# LNA.net
KiCad netlist of a schematic drawn in Altium Designer
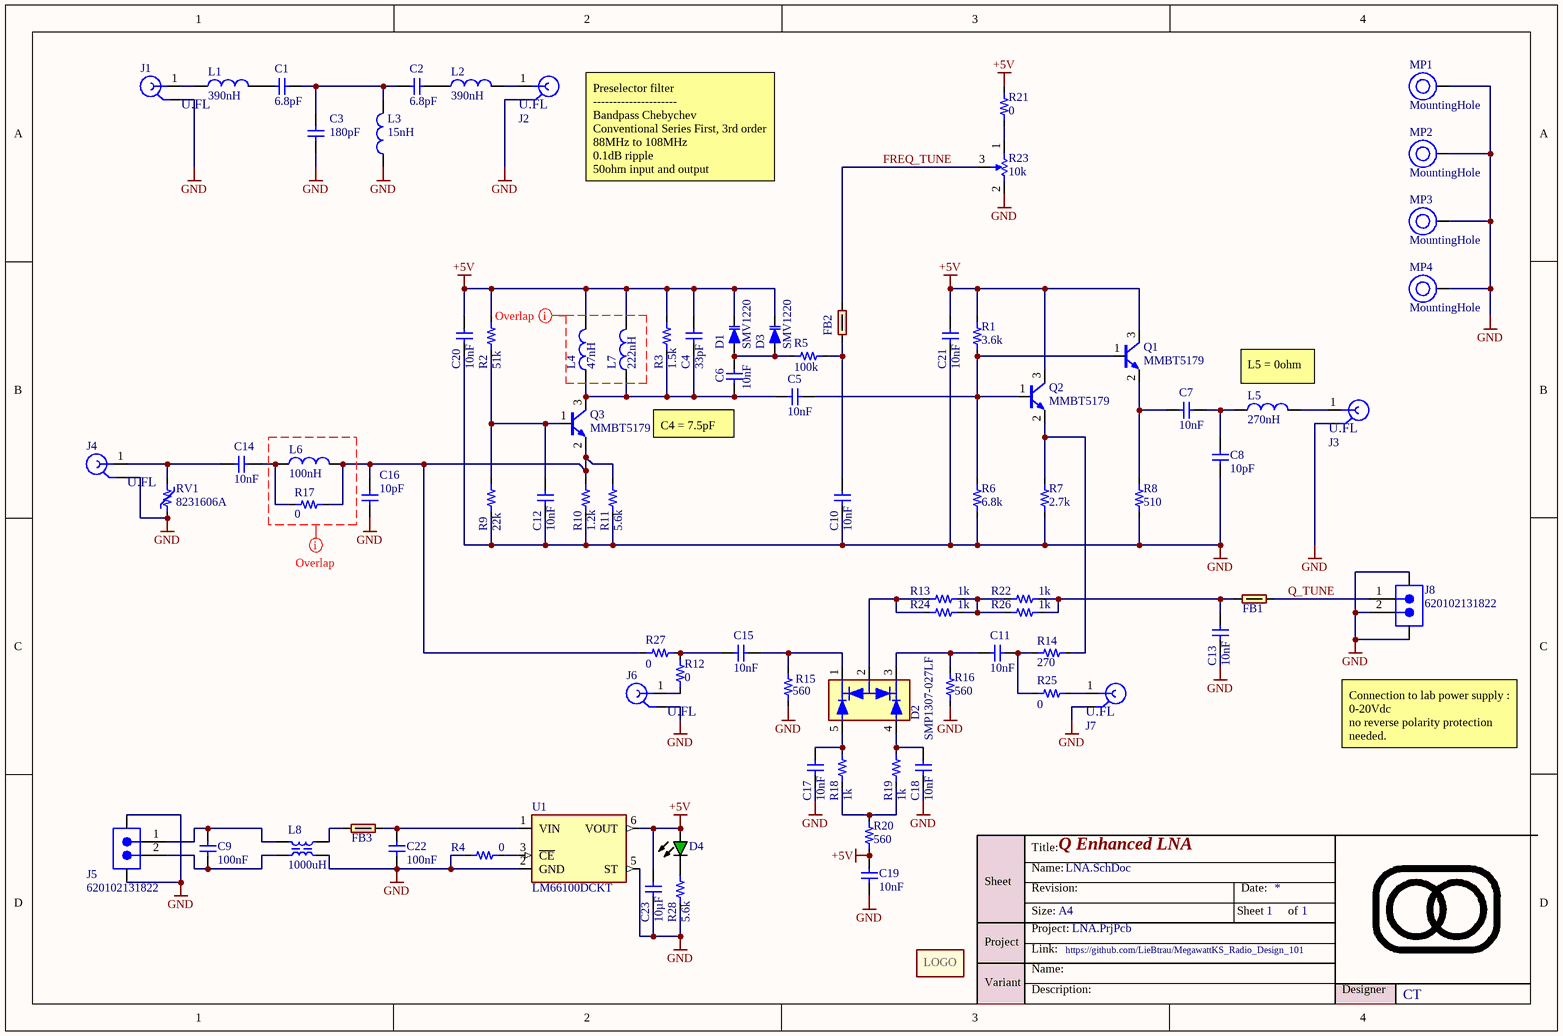
[diagram p0: LNA.SchDoc]

(export (version "E")
  (design (tool "Eeschema 10.0.6"))
  (components
    (comp (ref "C1")
      (value "6.8pF")
      (footprint "0603-C-N")
      (description "WCAP-CSGP Multilayer Ceramic Chip Capacitor, General Purpose, size 0603, NP0, 6.8pF, 50VDC")
      (fields
        (field (name "TOLERANCE") "0.5pF")
        (field (name "Comment") "Capacitor 6.8pF +/-0.5pF 50V NP0 0603")
      )
      (libsource (lib "7c7 Engineering") (part "CAP-NP-2"))
    )
    (comp (ref "C2")
      (value "6.8pF")
      (footprint "0603-C-N")
      (description "WCAP-CSGP Multilayer Ceramic Chip Capacitor, General Purpose, size 0603, NP0, 6.8pF, 50VDC")
      (fields
        (field (name "TOLERANCE") "0.5pF")
        (field (name "Comment") "Capacitor 6.8pF +/-0.5pF 50V NP0 0603")
      )
      (libsource (lib "7c7 Engineering") (part "CAP-NP-2"))
    )
    (comp (ref "C3")
      (value "180pF")
      (footprint "0603-C-N")
      (description "Cap Ceramic 180pF 100V C0G 5% SMD 0603 125°C Paper T/R")
      (fields (field (name "TOLERANCE") "5%") (field (name "JLCPCB PART #") "C107041"))
      (libsource (lib "7c7 Engineering") (part "CAP-NP-2"))
    )
    (comp (ref "C4")
      (value "33pF")
      (footprint "0603-C-N")
      (description "WCAP-CSGP Multilayer Ceramic Chip Capacitor, General Purpose, size 0603, NP0, 33pF, 50VDC")
      (fields (field (name "TOLERANCE") "5%") (field (name "Comment") "Capacitor 33pF +/-5% 50V NP0 0603"))
      (libsource (lib "7c7 Engineering") (part "CAP-NP-2"))
    )
    (comp (ref "C5")
      (value "10nF")
      (footprint "0603-C-N")
      (description "Multilayer Ceramic Capacitor, Grm Series, 0.01 F, 5%, C0g / Np0, 50 V, 0603 [1608 Metric]")
      (fields (field (name "VOLTAGE") "50V") (field (name "TOLERANCE") "5%"))
      (libsource (lib "7c7 Engineering") (part "CAP-NP-2"))
    )
    (comp (ref "C6")
      (value "10nF")
      (footprint "0603-C-N")
      (description "Multilayer Ceramic Capacitor, Grm Series, 0.01 F, 5%, C0g / Np0, 50 V, 0603 [1608 Metric]")
      (fields (field (name "VOLTAGE") "50V") (field (name "TOLERANCE") "5%"))
      (libsource (lib "7c7 Engineering") (part "CAP-NP-2"))
    )
    (comp (ref "C7")
      (value "10nF")
      (footprint "0603-C-N")
      (description "Multilayer Ceramic Capacitor, Grm Series, 0.01 F, 5%, C0g / Np0, 50 V, 0603 [1608 Metric]")
      (fields (field (name "VOLTAGE") "50V") (field (name "TOLERANCE") "5%"))
      (libsource (lib "7c7 Engineering") (part "CAP-NP-2"))
    )
    (comp (ref "C8")
      (value "10pF")
      (footprint "0603-C-N")
      (description "WCAP-CSGP Multilayer Ceramic Chip Capacitor, General Purpose, size 0603, NP0, 10pF, 50VDC")
      (fields (field (name "JLCPCB PART #") "C106245") (field (name "TOLERANCE") "5%"))
      (libsource (lib "7c7 Engineering") (part "CAP-NP-2"))
    )
    (comp (ref "C9")
      (value "100nF")
      (footprint "0603-C-N")
      (description "WCAP-CSGP Multilayer Ceramic Chip Capacitor, General Purpose, size 0603, X7R, 100nF, 50VDC")
      (fields (field (name "TOLERANCE") "10%") (field (name "JLCPCB PART #") "C14663"))
      (libsource (lib "7c7 Engineering") (part "CAP-NP-2"))
    )
    (comp (ref "C10")
      (value "10nF")
      (footprint "0603-C-N")
      (description "Multilayer Ceramic Capacitor, Grm Series, 0.01 F, 5%, C0g / Np0, 50 V, 0603 [1608 Metric]")
      (fields (field (name "VOLTAGE") "50V") (field (name "TOLERANCE") "5%"))
      (libsource (lib "7c7 Engineering") (part "CAP-NP-2"))
    )
    (comp (ref "C11")
      (value "10nF")
      (footprint "0603-C-N")
      (description "Multilayer Ceramic Capacitor, Grm Series, 0.01 F, 5%, C0g / Np0, 50 V, 0603 [1608 Metric]")
      (fields (field (name "VOLTAGE") "50V") (field (name "TOLERANCE") "5%"))
      (libsource (lib "7c7 Engineering") (part "CAP-NP-2"))
    )
    (comp (ref "C12")
      (value "10nF")
      (footprint "0603-C-N")
      (description "Multilayer Ceramic Capacitor, Grm Series, 0.01 F, 5%, C0g / Np0, 50 V, 0603 [1608 Metric]")
      (fields (field (name "VOLTAGE") "50V") (field (name "TOLERANCE") "5%"))
      (libsource (lib "7c7 Engineering") (part "CAP-NP-2"))
    )
    (comp (ref "C13")
      (value "10nF")
      (footprint "0603-C-N")
      (description "Multilayer Ceramic Capacitor, Grm Series, 0.01 F, 5%, C0g / Np0, 50 V, 0603 [1608 Metric]")
      (fields (field (name "VOLTAGE") "50V") (field (name "TOLERANCE") "5%"))
      (libsource (lib "7c7 Engineering") (part "CAP-NP-2"))
    )
    (comp (ref "C14")
      (value "10nF")
      (footprint "0603-C-N")
      (description "Multilayer Ceramic Capacitor, Grm Series, 0.01 F, 5%, C0g / Np0, 50 V, 0603 [1608 Metric]")
      (fields (field (name "VOLTAGE") "50V") (field (name "TOLERANCE") "5%"))
      (libsource (lib "7c7 Engineering") (part "CAP-NP-2"))
    )
    (comp (ref "C15")
      (value "10nF")
      (footprint "0603-C-N")
      (description "Multilayer Ceramic Capacitor, Grm Series, 0.01 F, 5%, C0g / Np0, 50 V, 0603 [1608 Metric]")
      (fields (field (name "VOLTAGE") "50V") (field (name "TOLERANCE") "5%"))
      (libsource (lib "7c7 Engineering") (part "CAP-NP-2"))
    )
    (comp (ref "C16")
      (value "10pF")
      (footprint "0603-C-N")
      (description "WCAP-CSGP Multilayer Ceramic Chip Capacitor, General Purpose, size 0603, NP0, 10pF, 50VDC")
      (fields (field (name "TOLERANCE") "5%") (field (name "JLCPCB PART #") "C106245"))
      (libsource (lib "7c7 Engineering") (part "CAP-NP-2"))
    )
    (comp (ref "C17")
      (value "10nF")
      (footprint "0603-C-N")
      (description "Multilayer Ceramic Capacitor, Grm Series, 0.01 F, 5%, C0g / Np0, 50 V, 0603 [1608 Metric]")
      (fields (field (name "VOLTAGE") "50V") (field (name "TOLERANCE") "5%"))
      (libsource (lib "7c7 Engineering") (part "CAP-NP-2"))
    )
    (comp (ref "C18")
      (value "10nF")
      (footprint "0603-C-N")
      (description "Multilayer Ceramic Capacitor, Grm Series, 0.01 F, 5%, C0g / Np0, 50 V, 0603 [1608 Metric]")
      (fields (field (name "VOLTAGE") "50V") (field (name "TOLERANCE") "5%"))
      (libsource (lib "7c7 Engineering") (part "CAP-NP-2"))
    )
    (comp (ref "C19")
      (value "10nF")
      (footprint "0603-C-N")
      (description "Multilayer Ceramic Capacitor, Grm Series, 0.01 F, 5%, C0g / Np0, 50 V, 0603 [1608 Metric]")
      (fields (field (name "VOLTAGE") "50V") (field (name "TOLERANCE") "5%"))
      (libsource (lib "7c7 Engineering") (part "CAP-NP-2"))
    )
    (comp (ref "C20")
      (value "10nF")
      (footprint "0603-C-N")
      (description "Multilayer Ceramic Capacitor, Grm Series, 0.01 F, 5%, C0g / Np0, 50 V, 0603 [1608 Metric]")
      (fields (field (name "VOLTAGE") "50V") (field (name "TOLERANCE") "5%"))
      (libsource (lib "7c7 Engineering") (part "CAP-NP-2"))
    )
    (comp (ref "C21")
      (value "10nF")
      (footprint "0603-C-N")
      (description "Multilayer Ceramic Capacitor, Grm Series, 0.01 F, 5%, C0g / Np0, 50 V, 0603 [1608 Metric]")
      (fields (field (name "VOLTAGE") "50V") (field (name "TOLERANCE") "5%"))
      (libsource (lib "7c7 Engineering") (part "CAP-NP-2"))
    )
    (comp (ref "C22")
      (value "100nF")
      (footprint "0603-C-N")
      (description "WCAP-CSGP Multilayer Ceramic Chip Capacitor, General Purpose, size 0603, X7R, 100nF, 50VDC")
      (fields (field (name "TOLERANCE") "10%") (field (name "JLCPCB PART #") "C14663"))
      (libsource (lib "7c7 Engineering") (part "CAP-NP-2"))
    )
    (comp (ref "C23")
      (value "10µF")
      (footprint "WCAP-CSGP_1210_L3.2W2.5H2.5")
      (description "WCAP-CSGP Multilayer Ceramic Chip Capacitor, General Purpose, size 1210, X7R, 10µF, 50VDC")
      (fields (field (name "JLCPCB PART #") "C77102") (field (name "TOLERANCE") "10%"))
      (libsource (lib "7c7 Engineering") (part "CAP-NP-2"))
    )
    (comp (ref "D1")
      (value "SMV1220")
      (footprint "FP-SOD523-MFG")
      (description "Diode, Varactor, SC79 N-Type")
      (fields (field (name "Comment") "SMV1220-079LF"))
      (libsource (lib "7c7 Engineering") (part "DIODE-VARACTOR"))
    )
    (comp (ref "D2")
      (value "SMP1307-027LF")
      (footprint "SOT25-N")
      (description "Dio Sw 0.85V 200V 10MA SOT5")
      (libsource (lib "7c7 Engineering") (part "SMP1307-027LF-Symbol-1"))
    )
    (comp (ref "D3")
      (value "SMV1220")
      (footprint "FP-SOD523-MFG")
      (description "Diode, Varactor, SC79 N-Type")
      (fields (field (name "Comment") "SMV1220-079LF"))
      (libsource (lib "7c7 Engineering") (part "DIODE-VARACTOR"))
    )
    (comp (ref "D4")
      (value "150060GS84000")
      (footprint "WL-SMCW_0603_150060xx8x000")
      (description "WL-SMCW Mono-color Chip LED Waterclear, size 0603, Green, 3.3V, 40°")
      (fields (field (name "JLCPCB PART #") "C7429914") (field (name "MANUFACTURER") "Wurth Elektronik"))
      (libsource (lib "7c7 Engineering") (part "LED-GREEN-2"))
    )
    (comp (ref "FB1")
      (value "742792662")
      (footprint "0603-FB-N")
      (description "WE-CBF SMT EMI Suppression Ferrite Bead, size 0603, 1000O, 0.83A")
      (fields (field (name "JLCPCB PART #") "C180490") (field (name "MANUFACTURER") "Wurth Elektronik"))
      (libsource (lib "") (part "IND_BEAD_1"))
    )
    (comp (ref "FB2")
      (value "742792662")
      (footprint "0603-FB-N")
      (description "WE-CBF SMT EMI Suppression Ferrite Bead, size 0603, 1000O, 0.83A")
      (fields (field (name "JLCPCB PART #") "C180490") (field (name "MANUFACTURER") "Wurth Elektronik"))
      (libsource (lib "7c7 Engineering") (part "IND_BEAD"))
    )
    (comp (ref "FB3")
      (value "742792662")
      (footprint "0603-FB-N")
      (description "WE-CBF SMT EMI Suppression Ferrite Bead, size 0603, 1000O, 0.83A")
      (fields (field (name "JLCPCB PART #") "C180490") (field (name "MANUFACTURER") "Wurth Elektronik"))
      (libsource (lib "") (part "IND_BEAD_1"))
    )
    (comp (ref "J1")
      (value "U.FL-R-SMT(10)")
      (footprint "HRS-U.FL-R-SMT_V")
      (fields (field (name "JLCPCB PART #") "C88373") (field (name "MANUFACTURER") "Hirose Electric"))
      (libsource (lib "") (part "CN_COAX_1"))
    )
    (comp (ref "J2")
      (value "U.FL-R-SMT(10)")
      (footprint "HRS-U.FL-R-SMT_V")
      (fields (field (name "JLCPCB PART #") "C88373") (field (name "MANUFACTURER") "Hirose Electric"))
      (libsource (lib "7c7 Engineering") (part "CN_COAX"))
    )
    (comp (ref "J3")
      (value "U.FL-R-SMT(10)")
      (footprint "HRS-U.FL-R-SMT_V")
      (fields (field (name "JLCPCB PART #") "C88373") (field (name "MANUFACTURER") "Hirose Electric"))
      (libsource (lib "7c7 Engineering") (part "CN_COAX"))
    )
    (comp (ref "J4")
      (value "U.FL-R-SMT(10)")
      (footprint "HRS-U.FL-R-SMT_V")
      (fields (field (name "JLCPCB PART #") "C88373") (field (name "MANUFACTURER") "Hirose Electric"))
      (libsource (lib "") (part "CN_COAX_1"))
    )
    (comp (ref "J5")
      (value "620102131822")
      (footprint "620102131822")
      (description "WR-WTB SMT Male Horizontal Shrouded Header, pitch 2mm, 2p")
      (fields
        (field (name "JLCPCB PART #") "C295747")
        (field (name "PAGE PART #") "K620102131822")
        (field (name "PUBLISHER") "Wurth Elektronik")
      )
      (libsource (lib "7c7 Engineering") (part "HDR_2P_2MP"))
    )
    (comp (ref "J6")
      (value "U.FL-R-SMT(10)")
      (footprint "HRS-U.FL-R-SMT_V")
      (fields (field (name "JLCPCB PART #") "C88373") (field (name "MANUFACTURER") "Hirose Electric"))
      (libsource (lib "") (part "CN_COAX_1"))
    )
    (comp (ref "J7")
      (value "U.FL-R-SMT(10)")
      (footprint "HRS-U.FL-R-SMT_V")
      (fields (field (name "JLCPCB PART #") "C88373") (field (name "MANUFACTURER") "Hirose Electric"))
      (libsource (lib "7c7 Engineering") (part "CN_COAX"))
    )
    (comp (ref "J8")
      (value "620102131822")
      (footprint "620102131822")
      (description "WR-WTB SMT Male Horizontal Shrouded Header, pitch 2mm, 2p")
      (fields
        (field (name "JLCPCB PART #") "C295747")
        (field (name "PAGE PART #") "K620102131822")
        (field (name "PUBLISHER") "Wurth Elektronik")
      )
      (libsource (lib "7c7 Engineering") (part "HDR_2P_2MP"))
    )
    (comp (ref "L1")
      (value "744762239GA")
      (footprint "WE-KI_1008")
      (description "WE-KI SMT Wire Wound Ceramic Inductor, size 1008, 390nH, 0.47A")
      (fields (field (name "INDUCTANCE") "390nH") (field (name "MANUFACTURER") "Wurth Elektronik"))
      (libsource (lib "7c7 Engineering") (part "IND"))
    )
    (comp (ref "L2")
      (value "744762239GA")
      (footprint "WE-KI_1008")
      (description "WE-KI SMT Wire Wound Ceramic Inductor, size 1008, 390nH, 0.47A")
      (fields (field (name "INDUCTANCE") "390nH") (field (name "MANUFACTURER") "Wurth Elektronik"))
      (libsource (lib "7c7 Engineering") (part "IND"))
    )
    (comp (ref "L3")
      (value "744762115GA")
      (footprint "WE-KI_1008")
      (description "WE-KI SMT Wire Wound Ceramic Inductor, size 1008, 15nH, 1A")
      (fields (field (name "INDUCTANCE") "15nH") (field (name "MANUFACTURER") "Wurth Elektronik"))
      (libsource (lib "7c7 Engineering") (part "IND"))
    )
    (comp (ref "L4")
      (value "744912147")
      (footprint "WE-CAIR_4248")
      (description "WE-CAIR SMT Air Coil, size 4248, 47nH, 3A, 5.6mO")
      (fields (field (name "MANUFACTURER") "Wurth Elektronik") (field (name "INDUCTANCE") "47nH"))
      (libsource (lib "7c7 Engineering") (part "IND"))
    )
    (comp (ref "L5")
      (value "744762227GA")
      (footprint "WE-KI_1008")
      (description "WE-KI SMT Wire Wound Ceramic Inductor, size 1008, 270nH, 0.6A")
      (fields (field (name "MANUFACTURER") "Wurth Elektronik") (field (name "INDUCTANCE") "270nH"))
      (libsource (lib "7c7 Engineering") (part "IND"))
    )
    (comp (ref "L6")
      (value "744762210GA")
      (footprint "WE-KI_1008")
      (description "WE-KI SMT Wire Wound Ceramic Inductor, size 1008, 100nH, 1A")
      (fields (field (name "MANUFACTURER") "Wurth Elektronik") (field (name "INDUCTANCE") "100nH"))
      (libsource (lib "7c7 Engineering") (part "IND"))
    )
    (comp (ref "L7")
      (value "744918222")
      (footprint "WE-CAIR_5910")
      (description "WE-CAIR SMT Air Coil, size 5910, 222nH, 3A, 35mO")
      (fields (field (name "INDUCTANCE") "222nH") (field (name "MANUFACTURER") "Wurth Elektronik"))
      (libsource (lib "7c7 Engineering") (part "IND"))
    )
    (comp (ref "L8")
      (value "744222")
      (footprint "WE-SL2_L9.2W6H5")
      (description "WE-SL2 SMT Common Mode Line Filter, 1000uH, 0.8A, 0.207Ohm")
      (fields
        (field (name "INDUCTANCE") "1000uH")
        (field (name "MANUFACTURER") "Wurth Elektronik")
        (field (name "JLCPCB PART #") "C2829007")
      )
      (libsource (lib "7c7 Engineering") (part "CM-choke"))
    )
    (comp (ref "M1")
      (value "Logo")
      (footprint "LOGO_9x6mm")
      (libsource (lib "Integrated_Library_LieBtrau") (part "Logo"))
    )
    (comp (ref "MP1")
      (value "MountingHole")
      (footprint "PTH-M3D6.5_VIA-RING")
      (libsource (lib "7c7 Engineering") (part "MECH_NO_BOM"))
    )
    (comp (ref "MP2")
      (value "MountingHole")
      (footprint "PTH-M3D6.5_VIA-RING")
      (libsource (lib "7c7 Engineering") (part "MECH_NO_BOM"))
    )
    (comp (ref "MP3")
      (value "MountingHole")
      (footprint "PTH-M3D6.5_VIA-RING")
      (libsource (lib "7c7 Engineering") (part "MECH_NO_BOM"))
    )
    (comp (ref "MP4")
      (value "MountingHole")
      (footprint "PTH-M3D6.5_VIA-RING")
      (libsource (lib "7c7 Engineering") (part "MECH_NO_BOM"))
    )
    (comp (ref "Q1")
      (value "MMBT5179")
      (footprint "SOT-23-3-N")
      (description "MMBT5179 Series 12 V CE Breakdown .05 A NPN RF Transistor - SOT-23")
      (fields (field (name "JLCPCB PART #") "C416012"))
      (libsource (lib "7c7 Engineering") (part "BJT-NPN-BEC"))
    )
    (comp (ref "Q2")
      (value "MMBT5179")
      (footprint "SOT-23-3-N")
      (description "MMBT5179 Series 12 V CE Breakdown .05 A NPN RF Transistor - SOT-23")
      (fields (field (name "JLCPCB PART #") "C416012"))
      (libsource (lib "7c7 Engineering") (part "BJT-NPN-BEC"))
    )
    (comp (ref "Q3")
      (value "MMBT5179")
      (footprint "SOT-23-3-N")
      (description "MMBT5179 Series 12 V CE Breakdown .05 A NPN RF Transistor - SOT-23")
      (fields (field (name "JLCPCB PART #") "C416012"))
      (libsource (lib "7c7 Engineering") (part "BJT-NPN-BEC"))
    )
    (comp (ref "R1")
      (value "3.6k")
      (footprint "0603-R-N")
      (description "Res Thick Film 0603 3.6K Ohm 1% 0.1W(1/10W) ±100ppm/°C Pad SMD T/R")
      (fields
        (field (name "JLCPCB PART #") "C22980")
        (field (name "Comment") "Resistor 3.6k +/-0.1W 1% 0603")
      )
      (libsource (lib "7c7 Engineering") (part "RES"))
    )
    (comp (ref "R2")
      (value "51k")
      (footprint "0603-R-N")
      (description "100Mw Thick Film Resistors 100Ppm/ 1% 51K 0603 Chip Resistor Surface Mount Rohs")
      (fields (field (name "TOLERANCE") "1%") (field (name "JLCPCB PART #") "C23196"))
      (libsource (lib "7c7 Engineering") (part "RES"))
    )
    (comp (ref "R3")
      (value "1.5k")
      (footprint "0603-R-N")
      (description "Chip Resistor, Thick Film, General Purpose, 0603, 100mW, 50V, 1.5 kOhm, +/-1%")
      (fields (field (name "TOLERANCE") "1%") (field (name "JLCPCB PART #") "C22843"))
      (libsource (lib "7c7 Engineering") (part "RES"))
    )
    (comp (ref "R4")
      (value "0")
      (footprint "0603-R-N")
      (description "Chip Jumper, Thick Film, Jumper, 0603, 100mW, 1A, 0 Ohm, <50 mOhm")
      (fields (field (name "FLIR PART #") "YRES0E-1") (field (name "TOLERANCE") "50 mOhm"))
      (libsource (lib "7c7 Engineering") (part "RES"))
    )
    (comp (ref "R5")
      (value "100k")
      (footprint "0603-R-N")
      (description "Chip Resistor, Thick Film, General Purpose, 0603, 100mW, 50V, 100 kOhm, +/-1%")
      (fields (field (name "TOLERANCE") "1%") (field (name "JLCPCB PART #") "C25803"))
      (libsource (lib "7c7 Engineering") (part "RES"))
    )
    (comp (ref "R6")
      (value "6.8k")
      (footprint "0603-R-N")
      (description "Res Thick Film 0603 6.8K Ohm 1% 0.1W(1/10W) ±100ppm/C Pad SMD T/R")
      (fields (field (name "TOLERANCE") "1%") (field (name "JLCPCB PART #") "C23212"))
      (libsource (lib "7c7 Engineering") (part "RES"))
    )
    (comp (ref "R7")
      (value "2.7k")
      (footprint "0603-R-N")
      (description "Res Thick Film 0603 2.7K Ohm 1% 0.1W(1/10W) ±100ppm/C Pad SMD Automotive T/R")
      (fields (field (name "TOLERANCE") "1%") (field (name "JLCPCB PART #") "C13167"))
      (libsource (lib "7c7 Engineering") (part "RES"))
    )
    (comp (ref "R8")
      (value "510")
      (footprint "0603-R-N")
      (description "SMD Chip Resistor, 510 Ohm, ± 1%, 100 mW, 0603 [1608 Metric], Thick Film, General Purpose")
      (fields (field (name "JLCPCB PART #") "C23193") (field (name "TOLERANCE") "1%"))
      (libsource (lib "7c7 Engineering") (part "RES"))
    )
    (comp (ref "R9")
      (value "22k")
      (footprint "0603-R-N")
      (description "Chip Resistor, Thick Film, General Purpose, 0603, 100mW, 50V, 22 kOhm, +/-1%")
      (fields (field (name "TOLERANCE") "1%") (field (name "JLCPCB PART #") "C31850"))
      (libsource (lib "7c7 Engineering") (part "RES"))
    )
    (comp (ref "R10")
      (value "1.2k")
      (footprint "0603-R-N")
      (description "Chip Resistor, Thick Film, General Purpose, 0603, 100mW, 50V, 1.2 kOhm, +/-1%")
      (fields (field (name "JLCPCB PART #") "C22765") (field (name "TOLERANCE") "1%"))
      (libsource (lib "7c7 Engineering") (part "RES"))
    )
    (comp (ref "R11")
      (value "5.6k")
      (footprint "0603-R-N")
      (description "Res Thick Film 0603 5.6K Ohm 1% 0.1W(1/10W) ±100ppm/C Pad SMD T/R")
      (fields (field (name "JLCPCB PART #") "C23189") (field (name "TOLERANCE") "1%"))
      (libsource (lib "7c7 Engineering") (part "RES"))
    )
    (comp (ref "R12")
      (value "0")
      (footprint "0603-R-N")
      (description "Chip Jumper, Thick Film, Jumper, 0603, 100mW, 1A, 0 Ohm, <50 mOhm")
      (fields (field (name "FLIR PART #") "YRES0E-1") (field (name "TOLERANCE") "50 mOhm"))
      (libsource (lib "7c7 Engineering") (part "RES"))
    )
    (comp (ref "R13")
      (value "1k")
      (footprint "0603-R-N")
      (description "Chip Resistor, Thick Film, General Purpose, 0603, 100mW, 50V, 1 kOhm, +/-1%")
      (fields (field (name "JLCPCB PART #") "C21190") (field (name "TOLERANCE") "1%"))
      (libsource (lib "7c7 Engineering") (part "RES"))
    )
    (comp (ref "R14")
      (value "270")
      (footprint "0603-R-N")
      (description "Chip Resistor, Thick Film, General Purpose, 0603, 100mW, 50V, 270 Ohm, +/-1%")
      (fields (field (name "TOLERANCE") "1%") (field (name "JLCPCB PART #") "C22966"))
      (libsource (lib "7c7 Engineering") (part "RES"))
    )
    (comp (ref "R15")
      (value "560")
      (footprint "0603-R-N")
      (description "SMD Chip Resistor, 560 Ohm, ï¿½ 1%, 100 mW, 0603 [1608 Metric], Thick Film, General Purpose")
      (fields (field (name "JLCPCB PART #") "C23204") (field (name "TOLERANCE") "1%"))
      (libsource (lib "7c7 Engineering") (part "RES"))
    )
    (comp (ref "R16")
      (value "560")
      (footprint "0603-R-N")
      (description "SMD Chip Resistor, 560 Ohm, ï¿½ 1%, 100 mW, 0603 [1608 Metric], Thick Film, General Purpose")
      (fields (field (name "JLCPCB PART #") "C23204") (field (name "TOLERANCE") "1%"))
      (libsource (lib "7c7 Engineering") (part "RES"))
    )
    (comp (ref "R17")
      (value "0")
      (footprint "0805-R-N")
      (description "Chip Jumper, Thick Film, Jumper, 0805, 125mW, 2A, 0 Ohm, <50 mOhm")
      (fields (field (name "TOLERANCE") "50 mOhm") (field (name "Comment") "Jumper 0R <50 mOhm 2A 0805"))
      (libsource (lib "7c7 Engineering") (part "RES"))
    )
    (comp (ref "R18")
      (value "1k")
      (footprint "0603-R-N")
      (description "Chip Resistor, Thick Film, General Purpose, 0603, 100mW, 50V, 1 kOhm, +/-1%")
      (fields (field (name "JLCPCB PART #") "C21190") (field (name "TOLERANCE") "1%"))
      (libsource (lib "7c7 Engineering") (part "RES"))
    )
    (comp (ref "R19")
      (value "1k")
      (footprint "0603-R-N")
      (description "Chip Resistor, Thick Film, General Purpose, 0603, 100mW, 50V, 1 kOhm, +/-1%")
      (fields (field (name "JLCPCB PART #") "C21190") (field (name "TOLERANCE") "1%"))
      (libsource (lib "7c7 Engineering") (part "RES"))
    )
    (comp (ref "R20")
      (value "560")
      (footprint "0603-R-N")
      (description "SMD Chip Resistor, 560 Ohm, ï¿½ 1%, 100 mW, 0603 [1608 Metric], Thick Film, General Purpose")
      (fields (field (name "JLCPCB PART #") "C23204") (field (name "TOLERANCE") "1%"))
      (libsource (lib "7c7 Engineering") (part "RES"))
    )
    (comp (ref "R21")
      (value "0")
      (footprint "0603-R-N")
      (description "Chip Jumper, Thick Film, Jumper, 0603, 100mW, 1A, 0 Ohm, <50 mOhm")
      (fields (field (name "FLIR PART #") "YRES0E-1") (field (name "TOLERANCE") "50 mOhm"))
      (libsource (lib "7c7 Engineering") (part "RES"))
    )
    (comp (ref "R22")
      (value "1k")
      (footprint "0603-R-N")
      (description "Chip Resistor, Thick Film, General Purpose, 0603, 100mW, 50V, 1 kOhm, +/-1%")
      (fields (field (name "JLCPCB PART #") "C21190") (field (name "TOLERANCE") "1%"))
      (libsource (lib "7c7 Engineering") (part "RES"))
    )
    (comp (ref "R23")
      (value "10k")
      (footprint "BOUR-3296W")
      (fields
        (field (name "JLCPCB PART #") "C34846")
        (field (name "TOLERANCE") "10%")
        (field (name "Comment") "3296W-1-103LF")
      )
      (libsource (lib "7c7 Engineering") (part "RES-ADJ-3"))
    )
    (comp (ref "R24")
      (value "1k")
      (footprint "0603-R-N")
      (description "Chip Resistor, Thick Film, General Purpose, 0603, 100mW, 50V, 1 kOhm, +/-1%")
      (fields (field (name "JLCPCB PART #") "C21190") (field (name "TOLERANCE") "1%"))
      (libsource (lib "7c7 Engineering") (part "RES"))
    )
    (comp (ref "R25")
      (value "0")
      (footprint "0603-R-N")
      (description "Chip Jumper, Thick Film, Jumper, 0603, 100mW, 1A, 0 Ohm, <50 mOhm")
      (fields (field (name "FLIR PART #") "YRES0E-1") (field (name "TOLERANCE") "50 mOhm"))
      (libsource (lib "7c7 Engineering") (part "RES"))
    )
    (comp (ref "R26")
      (value "1k")
      (footprint "0603-R-N")
      (description "Chip Resistor, Thick Film, General Purpose, 0603, 100mW, 50V, 1 kOhm, +/-1%")
      (fields (field (name "JLCPCB PART #") "C21190") (field (name "TOLERANCE") "1%"))
      (libsource (lib "7c7 Engineering") (part "RES"))
    )
    (comp (ref "R27")
      (value "0")
      (footprint "0603-R-N")
      (description "Chip Jumper, Thick Film, Jumper, 0603, 100mW, 1A, 0 Ohm, <50 mOhm")
      (fields (field (name "FLIR PART #") "YRES0E-1") (field (name "TOLERANCE") "50 mOhm"))
      (libsource (lib "7c7 Engineering") (part "RES"))
    )
    (comp (ref "R28")
      (value "5.6k")
      (footprint "0603-R-N")
      (description "Res Thick Film 0603 5.6K Ohm 1% 0.1W(1/10W) ±100ppm/C Pad SMD T/R")
      (fields (field (name "JLCPCB PART #") "C23189") (field (name "TOLERANCE") "1%"))
      (libsource (lib "7c7 Engineering") (part "RES"))
    )
    (comp (ref "RV1")
      (value "8231606A")
      (footprint "0603-VAR-N")
      (description "WE-VE femtoF ESD Suppressor, size 0603, 6VDC, 0.05pF")
      (fields (field (name "MANUFACTURER") "Wurth Elektronik"))
      (libsource (lib "7c7 Engineering") (part "RES_VARISTOR"))
    )
    (comp (ref "U1")
      (value "LM66100DCKT")
      (footprint "SOT-363-N")
      (description "1.5-V to 5.5-V, 1.5-A, 0.5-µA IQ ideal diode with integrated FET 6-SC70 -40 to 105")
      (libsource (lib "7c7 Engineering") (part "IC_LM66100"))
    )
  )
  (nets
    (net (code "1") (name "+5V") (class "Default")
      (node (ref "C19") (pin "1") (pinfunction "1_1") (pintype "passive"))
      (node (ref "C20") (pin "1") (pinfunction "1_1") (pintype "passive"))
      (node (ref "C21") (pin "1") (pinfunction "1_1") (pintype "passive"))
      (node (ref "C23") (pin "2") (pinfunction "2_2") (pintype "passive"))
      (node (ref "C4") (pin "2") (pinfunction "2_2") (pintype "passive"))
      (node (ref "D1") (pin "1") (pinfunction "K_1") (pintype "passive"))
      (node (ref "D3") (pin "1") (pinfunction "K_1") (pintype "passive"))
      (node (ref "D4") (pin "2") (pinfunction "A_2") (pintype "passive"))
      (node (ref "L4") (pin "2") (pinfunction "2_2") (pintype "passive"))
      (node (ref "L7") (pin "2") (pinfunction "2_2") (pintype "passive"))
      (node (ref "Q1") (pin "3") (pinfunction "C_3") (pintype "passive"))
      (node (ref "Q2") (pin "3") (pinfunction "C_3") (pintype "passive"))
      (node (ref "R1") (pin "2") (pinfunction "2_2") (pintype "passive"))
      (node (ref "R2") (pin "2") (pinfunction "2_2") (pintype "passive"))
      (node (ref "R20") (pin "1") (pinfunction "1_1") (pintype "passive"))
      (node (ref "R21") (pin "2") (pinfunction "2_2") (pintype "passive"))
      (node (ref "R3") (pin "2") (pinfunction "2_2") (pintype "passive"))
      (node (ref "U1") (pin "6") (pinfunction "VOUT_6") (pintype "output"))
    )
    (net (code "2") (name "/FREQ_TUNE") (class "Default")
      (node (ref "FB2") (pin "2") (pinfunction "2_2") (pintype "passive"))
      (node (ref "R23") (pin "3") (pinfunction "TAP_3") (pintype "passive"))
    )
    (net (code "3") (name "/Q_TUNE") (class "Default")
      (node (ref "FB1") (pin "1") (pinfunction "1_1") (pintype "passive"))
      (node (ref "J8") (pin "1") (pinfunction "1_1") (pintype "passive"))
    )
    (net (code "4") (name "GND") (class "Default")
      (node (ref "C10") (pin "2") (pinfunction "2_2") (pintype "passive"))
      (node (ref "C12") (pin "2") (pinfunction "2_2") (pintype "passive"))
      (node (ref "C13") (pin "1") (pinfunction "1_1") (pintype "passive"))
      (node (ref "C16") (pin "1") (pinfunction "1_1") (pintype "passive"))
      (node (ref "C17") (pin "2") (pinfunction "2_2") (pintype "passive"))
      (node (ref "C18") (pin "1") (pinfunction "1_1") (pintype "passive"))
      (node (ref "C19") (pin "2") (pinfunction "2_2") (pintype "passive"))
      (node (ref "C20") (pin "2") (pinfunction "2_2") (pintype "passive"))
      (node (ref "C21") (pin "2") (pinfunction "2_2") (pintype "passive"))
      (node (ref "C22") (pin "1") (pinfunction "1_1") (pintype "passive"))
      (node (ref "C23") (pin "1") (pinfunction "1_1") (pintype "passive"))
      (node (ref "C3") (pin "1") (pinfunction "1_1") (pintype "passive"))
      (node (ref "C8") (pin "2") (pinfunction "2_2") (pintype "passive"))
      (node (ref "J1") (pin "2") (pinfunction "GND_2") (pintype "passive"))
      (node (ref "J2") (pin "2") (pinfunction "GND_2") (pintype "passive"))
      (node (ref "J3") (pin "2") (pinfunction "GND_2") (pintype "passive"))
      (node (ref "J4") (pin "2") (pinfunction "GND_2") (pintype "passive"))
      (node (ref "J5") (pin "MP1") (pinfunction "MP1_MP1") (pintype "passive"))
      (node (ref "J5") (pin "MP2") (pinfunction "MP2_MP2") (pintype "passive"))
      (node (ref "J6") (pin "2") (pinfunction "GND_2") (pintype "passive"))
      (node (ref "J7") (pin "2") (pinfunction "GND_2") (pintype "passive"))
      (node (ref "J8") (pin "2") (pinfunction "2_2") (pintype "passive"))
      (node (ref "J8") (pin "MP1") (pinfunction "MP1_MP1") (pintype "passive"))
      (node (ref "J8") (pin "MP2") (pinfunction "MP2_MP2") (pintype "passive"))
      (node (ref "L3") (pin "1") (pinfunction "1_1") (pintype "passive"))
      (node (ref "L8") (pin "3") (pinfunction "3_3") (pintype "passive"))
      (node (ref "MP1") (pin "1") (pinfunction "H1_1") (pintype "passive"))
      (node (ref "MP2") (pin "1") (pinfunction "H1_1") (pintype "passive"))
      (node (ref "MP3") (pin "1") (pinfunction "H1_1") (pintype "passive"))
      (node (ref "MP4") (pin "1") (pinfunction "H1_1") (pintype "passive"))
      (node (ref "R10") (pin "1") (pinfunction "1_1") (pintype "passive"))
      (node (ref "R11") (pin "1") (pinfunction "1_1") (pintype "passive"))
      (node (ref "R15") (pin "1") (pinfunction "1_1") (pintype "passive"))
      (node (ref "R16") (pin "1") (pinfunction "1_1") (pintype "passive"))
      (node (ref "R23") (pin "2") (pinfunction "B_2") (pintype "passive"))
      (node (ref "R28") (pin "1") (pinfunction "1_1") (pintype "passive"))
      (node (ref "R4") (pin "2") (pinfunction "2_2") (pintype "passive"))
      (node (ref "R6") (pin "1") (pinfunction "1_1") (pintype "passive"))
      (node (ref "R7") (pin "1") (pinfunction "1_1") (pintype "passive"))
      (node (ref "R8") (pin "1") (pinfunction "1_1") (pintype "passive"))
      (node (ref "R9") (pin "1") (pinfunction "1_1") (pintype "passive"))
      (node (ref "RV1") (pin "1") (pinfunction "1_1") (pintype "passive"))
      (node (ref "U1") (pin "2") (pinfunction "GND_2") (pintype "power_in"))
      (node (ref "U1") (pin "5") (pinfunction "ST_5") (pintype "output"))
    )
    (net (code "5") (name "Net-(C1-Pad1)") (class "Default")
      (node (ref "C1") (pin "1") (pinfunction "1_1") (pintype "passive"))
      (node (ref "C2") (pin "2") (pinfunction "2_2") (pintype "passive"))
      (node (ref "C3") (pin "2") (pinfunction "2_2") (pintype "passive"))
      (node (ref "L3") (pin "2") (pinfunction "2_2") (pintype "passive"))
    )
    (net (code "6") (name "Net-(C1-Pad2)") (class "Default")
      (node (ref "C1") (pin "2") (pinfunction "2_2") (pintype "passive"))
      (node (ref "L1") (pin "2") (pinfunction "2_2") (pintype "passive"))
    )
    (net (code "7") (name "Net-(C2-Pad1)") (class "Default")
      (node (ref "C2") (pin "1") (pinfunction "1_1") (pintype "passive"))
      (node (ref "L2") (pin "1") (pinfunction "1_1") (pintype "passive"))
    )
    (net (code "8") (name "Net-(C7-Pad2)") (class "Default")
      (node (ref "C7") (pin "2") (pinfunction "2_2") (pintype "passive"))
      (node (ref "C8") (pin "1") (pinfunction "1_1") (pintype "passive"))
      (node (ref "L5") (pin "1") (pinfunction "1_1") (pintype "passive"))
    )
    (net (code "9") (name "Net-(C9-Pad1)") (class "Default")
      (node (ref "C9") (pin "1") (pinfunction "1_1") (pintype "passive"))
      (node (ref "J5") (pin "2") (pinfunction "2_2") (pintype "passive"))
      (node (ref "L8") (pin "4") (pinfunction "4_4") (pintype "passive"))
    )
    (net (code "10") (name "Net-(C9-Pad2)") (class "Default")
      (node (ref "C9") (pin "2") (pinfunction "2_2") (pintype "passive"))
      (node (ref "J5") (pin "1") (pinfunction "1_1") (pintype "passive"))
      (node (ref "L8") (pin "1") (pinfunction "1_1") (pintype "passive"))
    )
    (net (code "11") (name "Net-(C10-Pad1)") (class "Default")
      (node (ref "C10") (pin "1") (pinfunction "1_1") (pintype "passive"))
      (node (ref "FB2") (pin "1") (pinfunction "1_1") (pintype "passive"))
      (node (ref "R5") (pin "2") (pinfunction "2_2") (pintype "passive"))
    )
    (net (code "12") (name "Net-(C11-Pad1)") (class "Default")
      (node (ref "C11") (pin "1") (pinfunction "1_1") (pintype "passive"))
      (node (ref "R14") (pin "1") (pinfunction "1_1") (pintype "passive"))
      (node (ref "R25") (pin "2") (pinfunction "2_2") (pintype "passive"))
    )
    (net (code "13") (name "Net-(C11-Pad2)") (class "Default")
      (node (ref "C11") (pin "2") (pinfunction "2_2") (pintype "passive"))
      (node (ref "D2") (pin "3") (pinfunction "3_3") (pintype "passive"))
      (node (ref "R16") (pin "2") (pinfunction "2_2") (pintype "passive"))
    )
    (net (code "14") (name "Net-(C13-Pad2)") (class "Default")
      (node (ref "C13") (pin "2") (pinfunction "2_2") (pintype "passive"))
      (node (ref "FB1") (pin "2") (pinfunction "2_2") (pintype "passive"))
      (node (ref "R22") (pin "2") (pinfunction "2_2") (pintype "passive"))
      (node (ref "R26") (pin "2") (pinfunction "2_2") (pintype "passive"))
    )
    (net (code "15") (name "Net-(C14-Pad2)") (class "Default")
      (node (ref "C14") (pin "2") (pinfunction "2_2") (pintype "passive"))
      (node (ref "L6") (pin "1") (pinfunction "1_1") (pintype "passive"))
      (node (ref "R17") (pin "1") (pinfunction "1_1") (pintype "passive"))
    )
    (net (code "16") (name "Net-(C15-Pad1)") (class "Default")
      (node (ref "C15") (pin "1") (pinfunction "1_1") (pintype "passive"))
      (node (ref "D2") (pin "1") (pinfunction "1_1") (pintype "passive"))
      (node (ref "R15") (pin "2") (pinfunction "2_2") (pintype "passive"))
    )
    (net (code "17") (name "Net-(C15-Pad2)") (class "Default")
      (node (ref "C15") (pin "2") (pinfunction "2_2") (pintype "passive"))
      (node (ref "R12") (pin "2") (pinfunction "2_2") (pintype "passive"))
      (node (ref "R27") (pin "1") (pinfunction "1_1") (pintype "passive"))
    )
    (net (code "18") (name "Net-(C17-Pad1)") (class "Default")
      (node (ref "C17") (pin "1") (pinfunction "1_1") (pintype "passive"))
      (node (ref "D2") (pin "5") (pinfunction "5_5") (pintype "passive"))
      (node (ref "R18") (pin "1") (pinfunction "1_1") (pintype "passive"))
    )
    (net (code "19") (name "Net-(C18-Pad2)") (class "Default")
      (node (ref "C18") (pin "2") (pinfunction "2_2") (pintype "passive"))
      (node (ref "D2") (pin "4") (pinfunction "4_4") (pintype "passive"))
      (node (ref "R19") (pin "1") (pinfunction "1_1") (pintype "passive"))
    )
    (net (code "20") (name "Net-(D1-A)") (class "Default")
      (node (ref "C6") (pin "1") (pinfunction "1_1") (pintype "passive"))
      (node (ref "D1") (pin "2") (pinfunction "A_2") (pintype "passive"))
      (node (ref "D3") (pin "2") (pinfunction "A_2") (pintype "passive"))
      (node (ref "R5") (pin "1") (pinfunction "1_1") (pintype "passive"))
    )
    (net (code "21") (name "Net-(D2-Pad2)") (class "Default")
      (node (ref "D2") (pin "2") (pinfunction "2_2") (pintype "passive"))
      (node (ref "R13") (pin "1") (pinfunction "1_1") (pintype "passive"))
      (node (ref "R24") (pin "1") (pinfunction "1_1") (pintype "passive"))
    )
    (net (code "22") (name "Net-(D4-K)") (class "Default")
      (node (ref "D4") (pin "1") (pinfunction "K_1") (pintype "passive"))
      (node (ref "R28") (pin "2") (pinfunction "2_2") (pintype "passive"))
    )
    (net (code "23") (name "Net-(FB3-Pad2)") (class "Default")
      (node (ref "FB3") (pin "2") (pinfunction "2_2") (pintype "passive"))
      (node (ref "L8") (pin "2") (pinfunction "2_2") (pintype "passive"))
    )
    (net (code "24") (name "Net-(J1-SIG)") (class "Default")
      (node (ref "J1") (pin "1") (pinfunction "SIG_1") (pintype "passive"))
      (node (ref "L1") (pin "1") (pinfunction "1_1") (pintype "passive"))
    )
    (net (code "25") (name "Net-(J2-SIG)") (class "Default")
      (node (ref "J2") (pin "1") (pinfunction "SIG_1") (pintype "passive"))
      (node (ref "L2") (pin "2") (pinfunction "2_2") (pintype "passive"))
    )
    (net (code "26") (name "Net-(J3-SIG)") (class "Default")
      (node (ref "J3") (pin "1") (pinfunction "SIG_1") (pintype "passive"))
      (node (ref "L5") (pin "2") (pinfunction "2_2") (pintype "passive"))
    )
    (net (code "27") (name "Net-(J4-SIG)") (class "Default")
      (node (ref "C14") (pin "1") (pinfunction "1_1") (pintype "passive"))
      (node (ref "J4") (pin "1") (pinfunction "SIG_1") (pintype "passive"))
      (node (ref "RV1") (pin "2") (pinfunction "2_2") (pintype "passive"))
    )
    (net (code "28") (name "Net-(J6-SIG)") (class "Default")
      (node (ref "J6") (pin "1") (pinfunction "SIG_1") (pintype "passive"))
      (node (ref "R12") (pin "1") (pinfunction "1_1") (pintype "passive"))
    )
    (net (code "29") (name "Net-(J7-SIG)") (class "Default")
      (node (ref "J7") (pin "1") (pinfunction "SIG_1") (pintype "passive"))
      (node (ref "R25") (pin "1") (pinfunction "1_1") (pintype "passive"))
    )
    (net (code "30") (name "Net-(Q1-B)") (class "Default")
      (node (ref "C5") (pin "2") (pinfunction "2_2") (pintype "passive"))
      (node (ref "Q1") (pin "1") (pinfunction "B_1") (pintype "passive"))
      (node (ref "Q2") (pin "1") (pinfunction "B_1") (pintype "passive"))
      (node (ref "R1") (pin "1") (pinfunction "1_1") (pintype "passive"))
      (node (ref "R6") (pin "2") (pinfunction "2_2") (pintype "passive"))
    )
    (net (code "31") (name "Net-(Q1-E)") (class "Default")
      (node (ref "C7") (pin "1") (pinfunction "1_1") (pintype "passive"))
      (node (ref "Q1") (pin "2") (pinfunction "E_2") (pintype "passive"))
      (node (ref "R8") (pin "2") (pinfunction "2_2") (pintype "passive"))
    )
    (net (code "32") (name "Net-(Q2-E)") (class "Default")
      (node (ref "Q2") (pin "2") (pinfunction "E_2") (pintype "passive"))
      (node (ref "R14") (pin "2") (pinfunction "2_2") (pintype "passive"))
      (node (ref "R7") (pin "2") (pinfunction "2_2") (pintype "passive"))
    )
    (net (code "33") (name "Net-(Q3-B)") (class "Default")
      (node (ref "C12") (pin "1") (pinfunction "1_1") (pintype "passive"))
      (node (ref "Q3") (pin "1") (pinfunction "B_1") (pintype "passive"))
      (node (ref "R2") (pin "1") (pinfunction "1_1") (pintype "passive"))
      (node (ref "R9") (pin "2") (pinfunction "2_2") (pintype "passive"))
    )
    (net (code "34") (name "Net-(Q3-C)") (class "Default")
      (node (ref "C4") (pin "1") (pinfunction "1_1") (pintype "passive"))
      (node (ref "C5") (pin "1") (pinfunction "1_1") (pintype "passive"))
      (node (ref "C6") (pin "2") (pinfunction "2_2") (pintype "passive"))
      (node (ref "L4") (pin "1") (pinfunction "1_1") (pintype "passive"))
      (node (ref "L7") (pin "1") (pinfunction "1_1") (pintype "passive"))
      (node (ref "Q3") (pin "3") (pinfunction "C_3") (pintype "passive"))
      (node (ref "R3") (pin "1") (pinfunction "1_1") (pintype "passive"))
    )
    (net (code "35") (name "Net-(Q3-E)") (class "Default")
      (node (ref "C16") (pin "2") (pinfunction "2_2") (pintype "passive"))
      (node (ref "L6") (pin "2") (pinfunction "2_2") (pintype "passive"))
      (node (ref "Q3") (pin "2") (pinfunction "E_2") (pintype "passive"))
      (node (ref "R10") (pin "2") (pinfunction "2_2") (pintype "passive"))
      (node (ref "R11") (pin "2") (pinfunction "2_2") (pintype "passive"))
      (node (ref "R17") (pin "2") (pinfunction "2_2") (pintype "passive"))
      (node (ref "R27") (pin "2") (pinfunction "2_2") (pintype "passive"))
    )
    (net (code "36") (name "Net-(R13-Pad2)") (class "Default")
      (node (ref "R13") (pin "2") (pinfunction "2_2") (pintype "passive"))
      (node (ref "R22") (pin "1") (pinfunction "1_1") (pintype "passive"))
      (node (ref "R24") (pin "2") (pinfunction "2_2") (pintype "passive"))
      (node (ref "R26") (pin "1") (pinfunction "1_1") (pintype "passive"))
    )
    (net (code "37") (name "Net-(R18-Pad2)") (class "Default")
      (node (ref "R18") (pin "2") (pinfunction "2_2") (pintype "passive"))
      (node (ref "R19") (pin "2") (pinfunction "2_2") (pintype "passive"))
      (node (ref "R20") (pin "2") (pinfunction "2_2") (pintype "passive"))
    )
    (net (code "38") (name "Net-(R23-A)") (class "Default")
      (node (ref "R21") (pin "1") (pinfunction "1_1") (pintype "passive"))
      (node (ref "R23") (pin "1") (pinfunction "A_1") (pintype "passive"))
    )
    (net (code "39") (name "Net-(U1-VIN)") (class "Default")
      (node (ref "C22") (pin "2") (pinfunction "2_2") (pintype "passive"))
      (node (ref "FB3") (pin "1") (pinfunction "1_1") (pintype "passive"))
      (node (ref "U1") (pin "1") (pinfunction "VIN_1") (pintype "power_in"))
    )
    (net (code "40") (name "Net-(U1-~{CE})") (class "Default")
      (node (ref "R4") (pin "1") (pinfunction "1_1") (pintype "passive"))
      (node (ref "U1") (pin "3") (pinfunction "~{CE}_3") (pintype "input"))
    )
  )
)
